# Bank3-4-5_I_O.net
KiCad netlist of a schematic drawn in Altium Designer
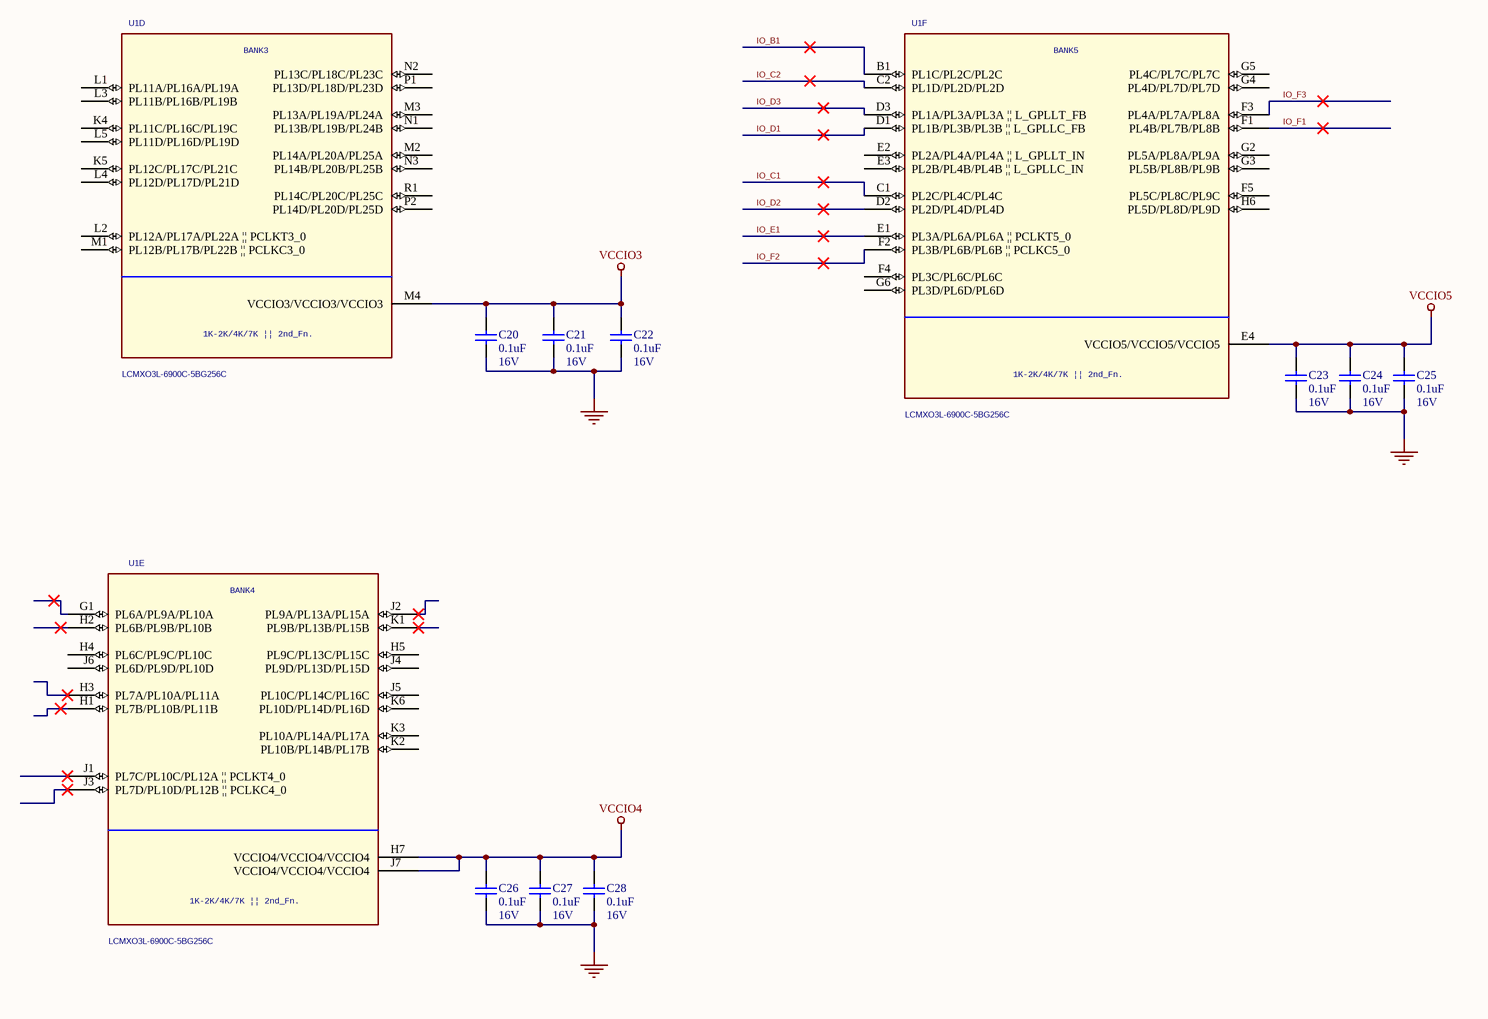
[diagram p0: Bank3-4-5_I_O.SchDoc]

(export (version "E")
  (design (tool "Eeschema 10.0.6"))
  (components
    (comp (ref "C20")
      (value "0.1uF")
      (footprint "CAPC1608X87X35ML15T15")
      (description "Ceramic Capacitor 0.1uF 16V +-10% X7R0603")
      (fields
        (field (name "PART NUMBER") "C0603C104M4RACTU")
        (field (name "MANUFACTURER") "Kemet")
        (field (name "VOLTAGE") "16V")
      )
      (libsource (lib "Altium Content Vault") (part "CAP"))
    )
    (comp (ref "C21")
      (value "0.1uF")
      (footprint "CAPC1608X87X35ML15T15")
      (description "Ceramic Capacitor 0.1uF 16V +-10% X7R0603")
      (fields
        (field (name "PART NUMBER") "C0603C104M4RACTU")
        (field (name "MANUFACTURER") "Kemet")
        (field (name "VOLTAGE") "16V")
      )
      (libsource (lib "Altium Content Vault") (part "CAP"))
    )
    (comp (ref "C22")
      (value "0.1uF")
      (footprint "CAPC1608X87X35ML15T15")
      (description "Ceramic Capacitor 0.1uF 16V +-10% X7R0603")
      (fields
        (field (name "PART NUMBER") "C0603C104M4RACTU")
        (field (name "MANUFACTURER") "Kemet")
        (field (name "VOLTAGE") "16V")
      )
      (libsource (lib "Altium Content Vault") (part "CAP"))
    )
    (comp (ref "C23")
      (value "0.1uF")
      (footprint "CAPC1608X87X35ML15T15")
      (description "Ceramic Capacitor 0.1uF 16V +-10% X7R0603")
      (fields
        (field (name "PART NUMBER") "C0603C104M4RACTU")
        (field (name "MANUFACTURER") "Kemet")
        (field (name "VOLTAGE") "16V")
      )
      (libsource (lib "Altium Content Vault") (part "CAP"))
    )
    (comp (ref "C24")
      (value "0.1uF")
      (footprint "CAPC1608X87X35ML15T15")
      (description "Ceramic Capacitor 0.1uF 16V +-10% X7R0603")
      (fields
        (field (name "PART NUMBER") "C0603C104M4RACTU")
        (field (name "MANUFACTURER") "Kemet")
        (field (name "VOLTAGE") "16V")
      )
      (libsource (lib "Altium Content Vault") (part "CAP"))
    )
    (comp (ref "C25")
      (value "0.1uF")
      (footprint "CAPC1608X87X35ML15T15")
      (description "Ceramic Capacitor 0.1uF 16V +-10% X7R0603")
      (fields
        (field (name "PART NUMBER") "C0603C104M4RACTU")
        (field (name "MANUFACTURER") "Kemet")
        (field (name "VOLTAGE") "16V")
      )
      (libsource (lib "Altium Content Vault") (part "CAP"))
    )
    (comp (ref "C26")
      (value "0.1uF")
      (footprint "CAPC1608X87X35ML15T15")
      (description "Ceramic Capacitor 0.1uF 16V +-10% X7R0603")
      (fields
        (field (name "PART NUMBER") "C0603C104M4RACTU")
        (field (name "MANUFACTURER") "Kemet")
        (field (name "VOLTAGE") "16V")
      )
      (libsource (lib "Altium Content Vault") (part "CAP"))
    )
    (comp (ref "C27")
      (value "0.1uF")
      (footprint "CAPC1608X87X35ML15T15")
      (description "Ceramic Capacitor 0.1uF 16V +-10% X7R0603")
      (fields
        (field (name "PART NUMBER") "C0603C104M4RACTU")
        (field (name "MANUFACTURER") "Kemet")
        (field (name "VOLTAGE") "16V")
      )
      (libsource (lib "Altium Content Vault") (part "CAP"))
    )
    (comp (ref "C28")
      (value "0.1uF")
      (footprint "CAPC1608X87X35ML15T15")
      (description "Ceramic Capacitor 0.1uF 16V +-10% X7R0603")
      (fields
        (field (name "PART NUMBER") "C0603C104M4RACTU")
        (field (name "MANUFACTURER") "Kemet")
        (field (name "VOLTAGE") "16V")
      )
      (libsource (lib "Altium Content Vault") (part "CAP"))
    )
    (comp (ref "U1")
      (value "LCMXO3L-6900C-5BG256C")
      (footprint "BGA256C80P16X16_1400X1400X170")
      (description "IC FPGA 6864LUTS 256BGA")
      (fields (field (name "MANUFACTURER") "Lattice semi"))
      (libsource (lib "*") (part "LCMXO3L-1K/2K/4K/7K-BG256"))
    )
  )
  (nets
    (net (code "1") (name "/IO_B1") (class "Default")
      (node (ref "U1") (pin "B1") (pinfunction "PL1C/PL2C/PL2C_B1") (pintype "bidirectional"))
    )
    (net (code "2") (name "/IO_C1") (class "Default")
      (node (ref "U1") (pin "C1") (pinfunction "PL2C/PL4C/PL4C_C1") (pintype "bidirectional"))
    )
    (net (code "3") (name "/IO_C2") (class "Default")
      (node (ref "U1") (pin "C2") (pinfunction "PL1D/PL2D/PL2D_C2") (pintype "bidirectional"))
    )
    (net (code "4") (name "/IO_D1") (class "Default")
      (node (ref "U1") (pin "D1") (pinfunction "PL1B/PL3B/PL3B_Ζ_L_GPLLC_FB_D1") (pintype "bidirectional"))
    )
    (net (code "5") (name "/IO_D2") (class "Default")
      (node (ref "U1") (pin "D2") (pinfunction "PL2D/PL4D/PL4D_D2") (pintype "bidirectional"))
    )
    (net (code "6") (name "/IO_D3") (class "Default")
      (node (ref "U1") (pin "D3") (pinfunction "PL1A/PL3A/PL3A_Ζ_L_GPLLT_FB_D3") (pintype "bidirectional"))
    )
    (net (code "7") (name "/IO_E1") (class "Default")
      (node (ref "U1") (pin "E1") (pinfunction "PL3A/PL6A/PL6A_Ζ_PCLKT5_0_E1") (pintype "bidirectional"))
    )
    (net (code "8") (name "/IO_F1") (class "Default")
      (node (ref "U1") (pin "F1") (pinfunction "PL4B/PL7B/PL8B_F1") (pintype "bidirectional"))
    )
    (net (code "9") (name "/IO_F2") (class "Default")
      (node (ref "U1") (pin "F2") (pinfunction "PL3B/PL6B/PL6B_Ζ_PCLKC5_0_F2") (pintype "bidirectional"))
    )
    (net (code "10") (name "/IO_F3") (class "Default")
      (node (ref "U1") (pin "F3") (pinfunction "PL4A/PL7A/PL8A_F3") (pintype "bidirectional"))
    )
    (net (code "11") (name "GND") (class "Default")
      (node (ref "C20") (pin "2") (pinfunction "2_2") (pintype "passive"))
      (node (ref "C21") (pin "2") (pinfunction "2_2") (pintype "passive"))
      (node (ref "C22") (pin "2") (pinfunction "2_2") (pintype "passive"))
      (node (ref "C23") (pin "2") (pinfunction "2_2") (pintype "passive"))
      (node (ref "C24") (pin "2") (pinfunction "2_2") (pintype "passive"))
      (node (ref "C25") (pin "2") (pinfunction "2_2") (pintype "passive"))
      (node (ref "C26") (pin "2") (pinfunction "2_2") (pintype "passive"))
      (node (ref "C27") (pin "2") (pinfunction "2_2") (pintype "passive"))
      (node (ref "C28") (pin "2") (pinfunction "2_2") (pintype "passive"))
    )
    (net (code "12") (name "VCCIO3") (class "Default")
      (node (ref "C20") (pin "1") (pinfunction "1_1") (pintype "passive"))
      (node (ref "C21") (pin "1") (pinfunction "1_1") (pintype "passive"))
      (node (ref "C22") (pin "1") (pinfunction "1_1") (pintype "passive"))
      (node (ref "U1") (pin "M4") (pinfunction "VCCIO3/VCCIO3/VCCIO3_M4") (pintype "power_in"))
    )
    (net (code "13") (name "VCCIO4") (class "Default")
      (node (ref "C26") (pin "1") (pinfunction "1_1") (pintype "passive"))
      (node (ref "C27") (pin "1") (pinfunction "1_1") (pintype "passive"))
      (node (ref "C28") (pin "1") (pinfunction "1_1") (pintype "passive"))
      (node (ref "U1") (pin "H7") (pinfunction "VCCIO4/VCCIO4/VCCIO4_H7") (pintype "power_in"))
      (node (ref "U1") (pin "J7") (pinfunction "VCCIO4/VCCIO4/VCCIO4_J7") (pintype "power_in"))
    )
    (net (code "14") (name "VCCIO5") (class "Default")
      (node (ref "C23") (pin "1") (pinfunction "1_1") (pintype "passive"))
      (node (ref "C24") (pin "1") (pinfunction "1_1") (pintype "passive"))
      (node (ref "C25") (pin "1") (pinfunction "1_1") (pintype "passive"))
      (node (ref "U1") (pin "E4") (pinfunction "VCCIO5/VCCIO5/VCCIO5_E4") (pintype "power_in"))
    )
    (net (code "15") (name "unconnected-(U1D-PL11A{slash}PL16A{slash}PL19A-PadL1)") (class "Default")
      (node (ref "U1") (pin "L1") (pinfunction "PL11A/PL16A/PL19A_L1") (pintype "bidirectional"))
    )
    (net (code "16") (name "unconnected-(U1D-PL11B{slash}PL16B{slash}PL19B-PadL3)") (class "Default")
      (node (ref "U1") (pin "L3") (pinfunction "PL11B/PL16B/PL19B_L3") (pintype "bidirectional"))
    )
    (net (code "17") (name "unconnected-(U1D-PL11C{slash}PL16C{slash}PL19C-PadK4)") (class "Default")
      (node (ref "U1") (pin "K4") (pinfunction "PL11C/PL16C/PL19C_K4") (pintype "bidirectional"))
    )
    (net (code "18") (name "unconnected-(U1D-PL11D{slash}PL16D{slash}PL19D-PadL5)") (class "Default")
      (node (ref "U1") (pin "L5") (pinfunction "PL11D/PL16D/PL19D_L5") (pintype "bidirectional"))
    )
    (net (code "19") (name "unconnected-(U1D-PL12A{slash}PL17A{slash}PL22A_Ζ_PCLKT3_0-PadL2)") (class "Default")
      (node (ref "U1") (pin "L2") (pinfunction "PL12A/PL17A/PL22A_Ζ_PCLKT3_0_L2") (pintype "bidirectional"))
    )
    (net (code "20") (name "unconnected-(U1D-PL12B{slash}PL17B{slash}PL22B_Ζ_PCLKC3_0-PadM1)") (class "Default")
      (node (ref "U1") (pin "M1") (pinfunction "PL12B/PL17B/PL22B_Ζ_PCLKC3_0_M1") (pintype "bidirectional"))
    )
    (net (code "21") (name "unconnected-(U1D-PL12C{slash}PL17C{slash}PL21C-PadK5)") (class "Default")
      (node (ref "U1") (pin "K5") (pinfunction "PL12C/PL17C/PL21C_K5") (pintype "bidirectional"))
    )
    (net (code "22") (name "unconnected-(U1D-PL12D{slash}PL17D{slash}PL21D-PadL4)") (class "Default")
      (node (ref "U1") (pin "L4") (pinfunction "PL12D/PL17D/PL21D_L4") (pintype "bidirectional"))
    )
    (net (code "23") (name "unconnected-(U1D-PL13A{slash}PL19A{slash}PL24A-PadM3)") (class "Default")
      (node (ref "U1") (pin "M3") (pinfunction "PL13A/PL19A/PL24A_M3") (pintype "bidirectional"))
    )
    (net (code "24") (name "unconnected-(U1D-PL13B{slash}PL19B{slash}PL24B-PadN1)") (class "Default")
      (node (ref "U1") (pin "N1") (pinfunction "PL13B/PL19B/PL24B_N1") (pintype "bidirectional"))
    )
    (net (code "25") (name "unconnected-(U1D-PL13C{slash}PL18C{slash}PL23C-PadN2)") (class "Default")
      (node (ref "U1") (pin "N2") (pinfunction "PL13C/PL18C/PL23C_N2") (pintype "bidirectional"))
    )
    (net (code "26") (name "unconnected-(U1D-PL13D{slash}PL18D{slash}PL23D-PadP1)") (class "Default")
      (node (ref "U1") (pin "P1") (pinfunction "PL13D/PL18D/PL23D_P1") (pintype "bidirectional"))
    )
    (net (code "27") (name "unconnected-(U1D-PL14A{slash}PL20A{slash}PL25A-PadM2)") (class "Default")
      (node (ref "U1") (pin "M2") (pinfunction "PL14A/PL20A/PL25A_M2") (pintype "bidirectional"))
    )
    (net (code "28") (name "unconnected-(U1D-PL14B{slash}PL20B{slash}PL25B-PadN3)") (class "Default")
      (node (ref "U1") (pin "N3") (pinfunction "PL14B/PL20B/PL25B_N3") (pintype "bidirectional"))
    )
    (net (code "29") (name "unconnected-(U1D-PL14C{slash}PL20C{slash}PL25C-PadR1)") (class "Default")
      (node (ref "U1") (pin "R1") (pinfunction "PL14C/PL20C/PL25C_R1") (pintype "bidirectional"))
    )
    (net (code "30") (name "unconnected-(U1D-PL14D{slash}PL20D{slash}PL25D-PadP2)") (class "Default")
      (node (ref "U1") (pin "P2") (pinfunction "PL14D/PL20D/PL25D_P2") (pintype "bidirectional"))
    )
    (net (code "31") (name "unconnected-(U1E-PL6A{slash}PL9A{slash}PL10A-PadG1)") (class "Default")
      (node (ref "U1") (pin "G1") (pinfunction "PL6A/PL9A/PL10A_G1") (pintype "bidirectional"))
    )
    (net (code "32") (name "unconnected-(U1E-PL6B{slash}PL9B{slash}PL10B-PadH2)") (class "Default")
      (node (ref "U1") (pin "H2") (pinfunction "PL6B/PL9B/PL10B_H2") (pintype "bidirectional"))
    )
    (net (code "33") (name "unconnected-(U1E-PL6C{slash}PL9C{slash}PL10C-PadH4)") (class "Default")
      (node (ref "U1") (pin "H4") (pinfunction "PL6C/PL9C/PL10C_H4") (pintype "bidirectional"))
    )
    (net (code "34") (name "unconnected-(U1E-PL6D{slash}PL9D{slash}PL10D-PadJ6)") (class "Default")
      (node (ref "U1") (pin "J6") (pinfunction "PL6D/PL9D/PL10D_J6") (pintype "bidirectional"))
    )
    (net (code "35") (name "unconnected-(U1E-PL7A{slash}PL10A{slash}PL11A-PadH3)") (class "Default")
      (node (ref "U1") (pin "H3") (pinfunction "PL7A/PL10A/PL11A_H3") (pintype "bidirectional+no_connect"))
    )
    (net (code "36") (name "unconnected-(U1E-PL7B{slash}PL10B{slash}PL11B-PadH1)") (class "Default")
      (node (ref "U1") (pin "H1") (pinfunction "PL7B/PL10B/PL11B_H1") (pintype "bidirectional"))
    )
    (net (code "37") (name "unconnected-(U1E-PL7C{slash}PL10C{slash}PL12A_Ζ_PCLKT4_0-PadJ1)") (class "Default")
      (node (ref "U1") (pin "J1") (pinfunction "PL7C/PL10C/PL12A_Ζ_PCLKT4_0_J1") (pintype "bidirectional+no_connect"))
    )
    (net (code "38") (name "unconnected-(U1E-PL7D{slash}PL10D{slash}PL12B_Ζ_PCLKC4_0-PadJ3)") (class "Default")
      (node (ref "U1") (pin "J3") (pinfunction "PL7D/PL10D/PL12B_Ζ_PCLKC4_0_J3") (pintype "bidirectional+no_connect"))
    )
    (net (code "39") (name "unconnected-(U1E-PL9A{slash}PL13A{slash}PL15A-PadJ2)") (class "Default")
      (node (ref "U1") (pin "J2") (pinfunction "PL9A/PL13A/PL15A_J2") (pintype "bidirectional+no_connect"))
    )
    (net (code "40") (name "unconnected-(U1E-PL9B{slash}PL13B{slash}PL15B-PadK1)") (class "Default")
      (node (ref "U1") (pin "K1") (pinfunction "PL9B/PL13B/PL15B_K1") (pintype "bidirectional+no_connect"))
    )
    (net (code "41") (name "unconnected-(U1E-PL9C{slash}PL13C{slash}PL15C-PadH5)") (class "Default")
      (node (ref "U1") (pin "H5") (pinfunction "PL9C/PL13C/PL15C_H5") (pintype "bidirectional"))
    )
    (net (code "42") (name "unconnected-(U1E-PL9D{slash}PL13D{slash}PL15D-PadJ4)") (class "Default")
      (node (ref "U1") (pin "J4") (pinfunction "PL9D/PL13D/PL15D_J4") (pintype "bidirectional"))
    )
    (net (code "43") (name "unconnected-(U1E-PL10A{slash}PL14A{slash}PL17A-PadK3)") (class "Default")
      (node (ref "U1") (pin "K3") (pinfunction "PL10A/PL14A/PL17A_K3") (pintype "bidirectional"))
    )
    (net (code "44") (name "unconnected-(U1E-PL10B{slash}PL14B{slash}PL17B-PadK2)") (class "Default")
      (node (ref "U1") (pin "K2") (pinfunction "PL10B/PL14B/PL17B_K2") (pintype "bidirectional"))
    )
    (net (code "45") (name "unconnected-(U1E-PL10C{slash}PL14C{slash}PL16C-PadJ5)") (class "Default")
      (node (ref "U1") (pin "J5") (pinfunction "PL10C/PL14C/PL16C_J5") (pintype "bidirectional"))
    )
    (net (code "46") (name "unconnected-(U1E-PL10D{slash}PL14D{slash}PL16D-PadK6)") (class "Default")
      (node (ref "U1") (pin "K6") (pinfunction "PL10D/PL14D/PL16D_K6") (pintype "bidirectional"))
    )
    (net (code "47") (name "unconnected-(U1F-PL2A{slash}PL4A{slash}PL4A_Ζ_L_GPLLT_IN-PadE2)") (class "Default")
      (node (ref "U1") (pin "E2") (pinfunction "PL2A/PL4A/PL4A_Ζ_L_GPLLT_IN_E2") (pintype "bidirectional"))
    )
    (net (code "48") (name "unconnected-(U1F-PL2B{slash}PL4B{slash}PL4B_Ζ_L_GPLLC_IN-PadE3)") (class "Default")
      (node (ref "U1") (pin "E3") (pinfunction "PL2B/PL4B/PL4B_Ζ_L_GPLLC_IN_E3") (pintype "bidirectional"))
    )
    (net (code "49") (name "unconnected-(U1F-PL3C{slash}PL6C{slash}PL6C-PadF4)") (class "Default")
      (node (ref "U1") (pin "F4") (pinfunction "PL3C/PL6C/PL6C_F4") (pintype "bidirectional"))
    )
    (net (code "50") (name "unconnected-(U1F-PL3D{slash}PL6D{slash}PL6D-PadG6)") (class "Default")
      (node (ref "U1") (pin "G6") (pinfunction "PL3D/PL6D/PL6D_G6") (pintype "bidirectional"))
    )
    (net (code "51") (name "unconnected-(U1F-PL4C{slash}PL7C{slash}PL7C-PadG5)") (class "Default")
      (node (ref "U1") (pin "G5") (pinfunction "PL4C/PL7C/PL7C_G5") (pintype "bidirectional"))
    )
    (net (code "52") (name "unconnected-(U1F-PL4D{slash}PL7D{slash}PL7D-PadG4)") (class "Default")
      (node (ref "U1") (pin "G4") (pinfunction "PL4D/PL7D/PL7D_G4") (pintype "bidirectional"))
    )
    (net (code "53") (name "unconnected-(U1F-PL5A{slash}PL8A{slash}PL9A-PadG2)") (class "Default")
      (node (ref "U1") (pin "G2") (pinfunction "PL5A/PL8A/PL9A_G2") (pintype "bidirectional"))
    )
    (net (code "54") (name "unconnected-(U1F-PL5B{slash}PL8B{slash}PL9B-PadG3)") (class "Default")
      (node (ref "U1") (pin "G3") (pinfunction "PL5B/PL8B/PL9B_G3") (pintype "bidirectional"))
    )
    (net (code "55") (name "unconnected-(U1F-PL5C{slash}PL8C{slash}PL9C-PadF5)") (class "Default")
      (node (ref "U1") (pin "F5") (pinfunction "PL5C/PL8C/PL9C_F5") (pintype "bidirectional"))
    )
    (net (code "56") (name "unconnected-(U1F-PL5D{slash}PL8D{slash}PL9D-PadH6)") (class "Default")
      (node (ref "U1") (pin "H6") (pinfunction "PL5D/PL8D/PL9D_H6") (pintype "bidirectional"))
    )
  )
)
